# I2Cbus.net
KiCad netlist of a schematic drawn in Altium Designer
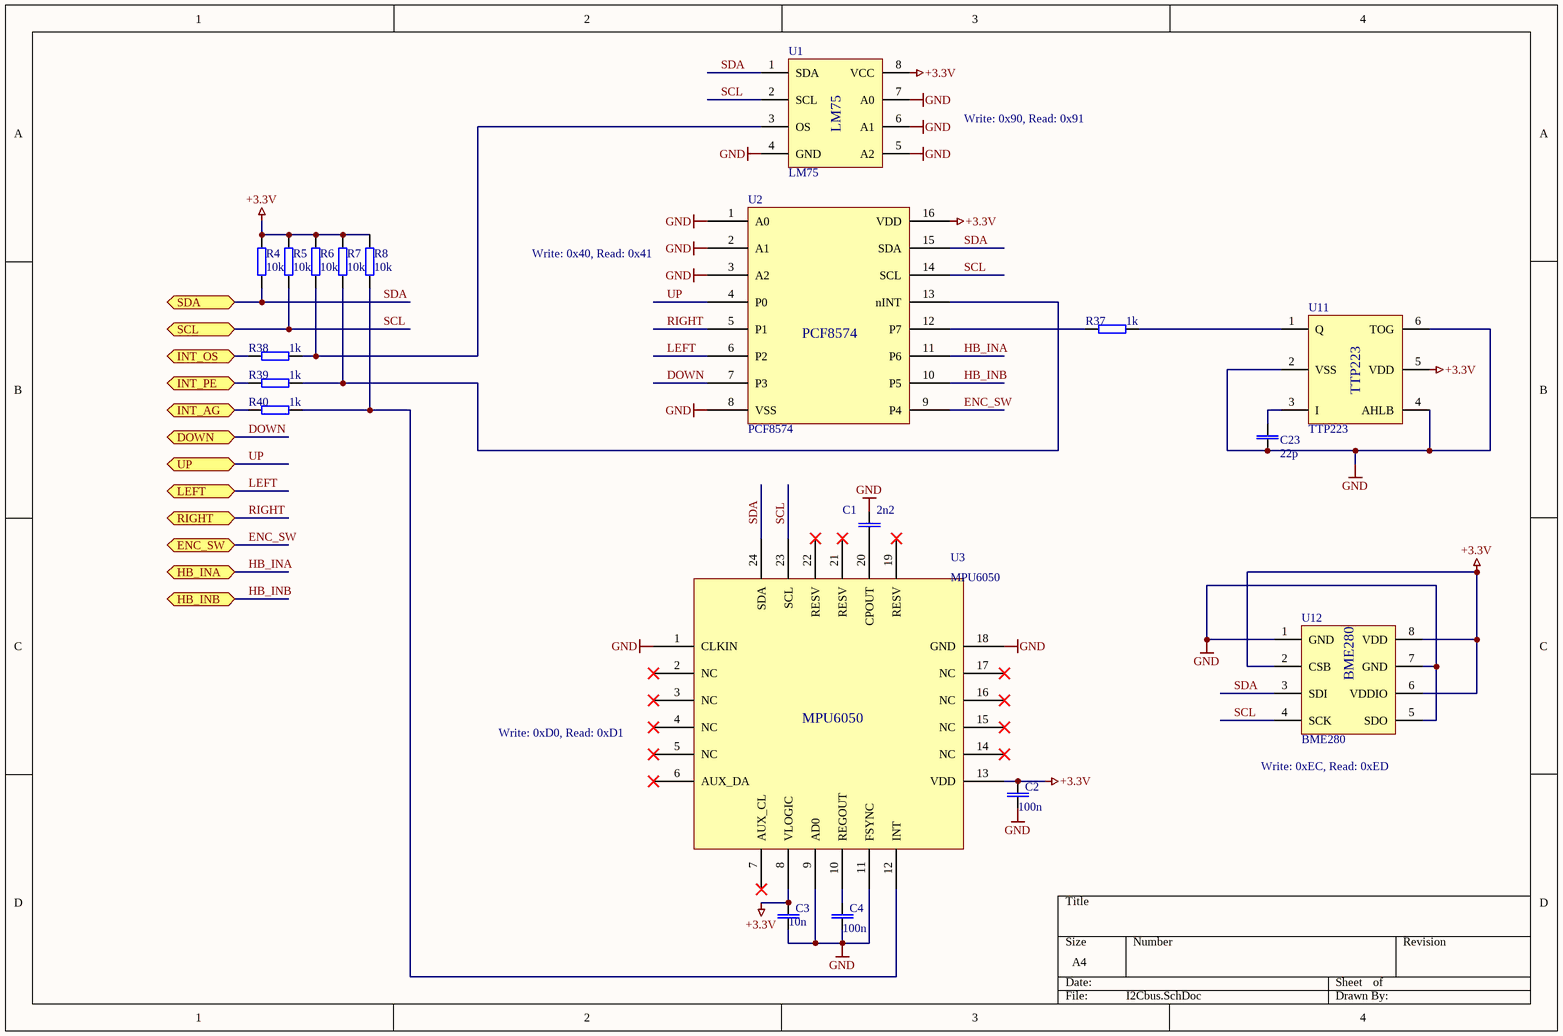
[diagram p0: I2Cbus.SchDoc]

(export (version "E")
  (design (tool "Eeschema 10.0.6"))
  (components
    (comp (ref "C1")
      (value "2n2")
      (footprint "CAP 0805")
      (description "NON POLARIZED CAPACITOR")
      (libsource (lib "SCH_LIB") (part "CAP"))
    )
    (comp (ref "C2")
      (value "100n")
      (footprint "CAP 0805")
      (description "NON POLARIZED CAPACITOR")
      (libsource (lib "SCH_LIB") (part "CAP"))
    )
    (comp (ref "C3")
      (value "10n")
      (footprint "CAP 0805")
      (description "NON POLARIZED CAPACITOR")
      (libsource (lib "SCH_LIB") (part "CAP"))
    )
    (comp (ref "C4")
      (value "100n")
      (footprint "CAP 0805")
      (description "NON POLARIZED CAPACITOR")
      (libsource (lib "SCH_LIB") (part "CAP"))
    )
    (comp (ref "C23")
      (value "22p")
      (footprint "CAP 0805")
      (description "NON POLARIZED CAPACITOR")
      (libsource (lib "SCH_LIB") (part "CAP"))
    )
    (comp (ref "R4")
      (value "10k")
      (footprint "RES 0805")
      (description "RESISTOR")
      (libsource (lib "") (part "RES_1"))
    )
    (comp (ref "R5")
      (value "10k")
      (footprint "RES 0805")
      (description "RESISTOR")
      (libsource (lib "") (part "RES_1"))
    )
    (comp (ref "R6")
      (value "10k")
      (footprint "RES 0805")
      (description "RESISTOR")
      (libsource (lib "") (part "RES_1"))
    )
    (comp (ref "R7")
      (value "10k")
      (footprint "RES 0805")
      (description "RESISTOR")
      (libsource (lib "") (part "RES_1"))
    )
    (comp (ref "R8")
      (value "10k")
      (footprint "RES 0805")
      (description "RESISTOR")
      (libsource (lib "") (part "RES_1"))
    )
    (comp (ref "R37")
      (value "1k")
      (footprint "RES 0805")
      (description "RESISTOR")
      (libsource (lib "SCH_LIB") (part "RES"))
    )
    (comp (ref "R38")
      (value "1k")
      (footprint "RES 0805")
      (description "RESISTOR")
      (libsource (lib "SCH_LIB") (part "RES"))
    )
    (comp (ref "R39")
      (value "1k")
      (footprint "RES 0805")
      (description "RESISTOR")
      (libsource (lib "SCH_LIB") (part "RES"))
    )
    (comp (ref "R40")
      (value "1k")
      (footprint "RES 0805")
      (description "RESISTOR")
      (libsource (lib "SCH_LIB") (part "RES"))
    )
    (comp (ref "U1")
      (value "LM75")
      (footprint "SO8")
      (description "Temperature sensor with I2C interface")
      (libsource (lib "SCH_LIB") (part "LM75"))
    )
    (comp (ref "U2")
      (value "PCF8574")
      (footprint "SO16W")
      (description "I/O expander I2C bus")
      (libsource (lib "SCH_LIB") (part "PCF8574"))
    )
    (comp (ref "U3")
      (value "MPU6050")
      (footprint "QFN24")
      (description "6 axis gyroscope and accelerometer sensor")
      (libsource (lib "SCH_LIB") (part "MPU6050"))
    )
    (comp (ref "U11")
      (value "TTP223")
      (footprint "SOT-23-6L")
      (description "1 KEY TOUCH PAD DETECTOR IC")
      (libsource (lib "SCH_LIB") (part "TTP223"))
    )
    (comp (ref "U12")
      (value "BME280")
      (footprint "BME280")
      (description "BME280 Environmental sensor")
      (libsource (lib "SCH_LIB") (part "BME280"))
    )
  )
  (nets
    (net (code "1") (name "+3.3V") (class "Default")
      (node (ref "C2") (pin "1") (pinfunction "1_1") (pintype "passive"))
      (node (ref "C3") (pin "1") (pinfunction "1_1") (pintype "passive"))
      (node (ref "R4") (pin "2") (pinfunction "2_2") (pintype "passive"))
      (node (ref "R5") (pin "2") (pinfunction "2_2") (pintype "passive"))
      (node (ref "R6") (pin "2") (pinfunction "2_2") (pintype "passive"))
      (node (ref "R7") (pin "2") (pinfunction "2_2") (pintype "passive"))
      (node (ref "R8") (pin "2") (pinfunction "2_2") (pintype "passive"))
      (node (ref "U1") (pin "8") (pinfunction "VCC_8") (pintype "passive"))
      (node (ref "U11") (pin "5") (pinfunction "VDD_5") (pintype "passive"))
      (node (ref "U12") (pin "2") (pinfunction "CSB_2") (pintype "passive"))
      (node (ref "U12") (pin "6") (pinfunction "VDDIO_6") (pintype "passive"))
      (node (ref "U12") (pin "8") (pinfunction "VDD_8") (pintype "passive"))
      (node (ref "U2") (pin "16") (pinfunction "VDD_16") (pintype "passive"))
      (node (ref "U3") (pin "13") (pinfunction "VDD_13") (pintype "passive"))
      (node (ref "U3") (pin "8") (pinfunction "VLOGIC_8") (pintype "passive"))
    )
    (net (code "2") (name "/DOWN") (class "Default")
      (node (ref "U2") (pin "7") (pinfunction "P3_7") (pintype "passive"))
    )
    (net (code "3") (name "/ENC_SW") (class "Default")
      (node (ref "U2") (pin "9") (pinfunction "P4_9") (pintype "passive"))
    )
    (net (code "4") (name "/HB_INA") (class "Default")
      (node (ref "U2") (pin "11") (pinfunction "P6_11") (pintype "passive"))
    )
    (net (code "5") (name "/HB_INB") (class "Default")
      (node (ref "U2") (pin "10") (pinfunction "P5_10") (pintype "passive"))
    )
    (net (code "6") (name "/INT_AG") (class "Default")
      (node (ref "R40") (pin "1") (pinfunction "1_1") (pintype "passive"))
    )
    (net (code "7") (name "/INT_OS") (class "Default")
      (node (ref "R38") (pin "1") (pinfunction "1_1") (pintype "passive"))
    )
    (net (code "8") (name "/INT_PE") (class "Default")
      (node (ref "R39") (pin "1") (pinfunction "1_1") (pintype "passive"))
    )
    (net (code "9") (name "/LEFT") (class "Default")
      (node (ref "U2") (pin "6") (pinfunction "P2_6") (pintype "passive"))
    )
    (net (code "10") (name "/RIGHT") (class "Default")
      (node (ref "U2") (pin "5") (pinfunction "P1_5") (pintype "passive"))
    )
    (net (code "11") (name "/SCL") (class "Default")
      (node (ref "R5") (pin "1") (pinfunction "1_1") (pintype "passive"))
      (node (ref "U1") (pin "2") (pinfunction "SCL_2") (pintype "passive"))
      (node (ref "U12") (pin "4") (pinfunction "SCK_4") (pintype "passive"))
      (node (ref "U2") (pin "14") (pinfunction "SCL_14") (pintype "passive"))
      (node (ref "U3") (pin "23") (pinfunction "SCL_23") (pintype "passive"))
    )
    (net (code "12") (name "/SDA") (class "Default")
      (node (ref "R4") (pin "1") (pinfunction "1_1") (pintype "passive"))
      (node (ref "U1") (pin "1") (pinfunction "SDA_1") (pintype "passive"))
      (node (ref "U12") (pin "3") (pinfunction "SDI_3") (pintype "passive"))
      (node (ref "U2") (pin "15") (pinfunction "SDA_15") (pintype "passive"))
      (node (ref "U3") (pin "24") (pinfunction "SDA_24") (pintype "passive"))
    )
    (net (code "13") (name "/UP") (class "Default")
      (node (ref "U2") (pin "4") (pinfunction "P0_4") (pintype "passive"))
    )
    (net (code "14") (name "GND") (class "Default")
      (node (ref "C1") (pin "2") (pinfunction "2_2") (pintype "passive"))
      (node (ref "C2") (pin "2") (pinfunction "2_2") (pintype "passive"))
      (node (ref "C23") (pin "2") (pinfunction "2_2") (pintype "passive"))
      (node (ref "C3") (pin "2") (pinfunction "2_2") (pintype "passive"))
      (node (ref "C4") (pin "2") (pinfunction "2_2") (pintype "passive"))
      (node (ref "U1") (pin "4") (pinfunction "GND_4") (pintype "passive"))
      (node (ref "U1") (pin "5") (pinfunction "A2_5") (pintype "passive"))
      (node (ref "U1") (pin "6") (pinfunction "A1_6") (pintype "passive"))
      (node (ref "U1") (pin "7") (pinfunction "A0_7") (pintype "passive"))
      (node (ref "U11") (pin "2") (pinfunction "VSS_2") (pintype "passive"))
      (node (ref "U11") (pin "4") (pinfunction "AHLB_4") (pintype "passive"))
      (node (ref "U11") (pin "6") (pinfunction "TOG_6") (pintype "passive"))
      (node (ref "U12") (pin "1") (pinfunction "GND_1") (pintype "passive"))
      (node (ref "U12") (pin "5") (pinfunction "SDO_5") (pintype "passive"))
      (node (ref "U12") (pin "7") (pinfunction "GND_7") (pintype "passive"))
      (node (ref "U2") (pin "1") (pinfunction "A0_1") (pintype "passive"))
      (node (ref "U2") (pin "2") (pinfunction "A1_2") (pintype "passive"))
      (node (ref "U2") (pin "3") (pinfunction "A2_3") (pintype "passive"))
      (node (ref "U2") (pin "8") (pinfunction "VSS_8") (pintype "passive"))
      (node (ref "U3") (pin "1") (pinfunction "CLKIN_1") (pintype "passive"))
      (node (ref "U3") (pin "11") (pinfunction "FSYNC_11") (pintype "passive"))
      (node (ref "U3") (pin "18") (pinfunction "GND_18") (pintype "passive"))
      (node (ref "U3") (pin "9") (pinfunction "AD0_9") (pintype "passive"))
    )
    (net (code "15") (name "Net-(U1-OS)") (class "Default")
      (node (ref "R38") (pin "2") (pinfunction "2_2") (pintype "passive"))
      (node (ref "R6") (pin "1") (pinfunction "1_1") (pintype "passive"))
      (node (ref "U1") (pin "3") (pinfunction "OS_3") (pintype "passive"))
    )
    (net (code "16") (name "Net-(U2-P7)") (class "Default")
      (node (ref "R37") (pin "1") (pinfunction "1_1") (pintype "passive"))
      (node (ref "U2") (pin "12") (pinfunction "P7_12") (pintype "passive"))
    )
    (net (code "17") (name "Net-(U2-nINT)") (class "Default")
      (node (ref "R39") (pin "2") (pinfunction "2_2") (pintype "passive"))
      (node (ref "R7") (pin "1") (pinfunction "1_1") (pintype "passive"))
      (node (ref "U2") (pin "13") (pinfunction "nINT_13") (pintype "passive"))
    )
    (net (code "18") (name "Net-(U3-CPOUT)") (class "Default")
      (node (ref "C1") (pin "1") (pinfunction "1_1") (pintype "passive"))
      (node (ref "U3") (pin "20") (pinfunction "CPOUT_20") (pintype "passive"))
    )
    (net (code "19") (name "Net-(U3-INT)") (class "Default")
      (node (ref "R40") (pin "2") (pinfunction "2_2") (pintype "passive"))
      (node (ref "R8") (pin "1") (pinfunction "1_1") (pintype "passive"))
      (node (ref "U3") (pin "12") (pinfunction "INT_12") (pintype "passive"))
    )
    (net (code "20") (name "Net-(U3-REGOUT)") (class "Default")
      (node (ref "C4") (pin "1") (pinfunction "1_1") (pintype "passive"))
      (node (ref "U3") (pin "10") (pinfunction "REGOUT_10") (pintype "passive"))
    )
    (net (code "21") (name "Net-(U11-I)") (class "Default")
      (node (ref "C23") (pin "1") (pinfunction "1_1") (pintype "passive"))
      (node (ref "U11") (pin "3") (pinfunction "I_3") (pintype "passive"))
    )
    (net (code "22") (name "Net-(U11-Q)") (class "Default")
      (node (ref "R37") (pin "2") (pinfunction "2_2") (pintype "passive"))
      (node (ref "U11") (pin "1") (pinfunction "Q_1") (pintype "passive"))
    )
    (net (code "23") (name "unconnected-(U3-AUX_CL-Pad7)") (class "Default")
      (node (ref "U3") (pin "7") (pinfunction "AUX_CL_7") (pintype "passive+no_connect"))
    )
    (net (code "24") (name "unconnected-(U3-AUX_DA-Pad6)") (class "Default")
      (node (ref "U3") (pin "6") (pinfunction "AUX_DA_6") (pintype "passive+no_connect"))
    )
    (net (code "25") (name "unconnected-(U3-NC-Pad2)") (class "Default")
      (node (ref "U3") (pin "2") (pinfunction "NC_2") (pintype "passive+no_connect"))
    )
    (net (code "26") (name "unconnected-(U3-NC-Pad3)") (class "Default")
      (node (ref "U3") (pin "3") (pinfunction "NC_3") (pintype "passive+no_connect"))
    )
    (net (code "27") (name "unconnected-(U3-NC-Pad4)") (class "Default")
      (node (ref "U3") (pin "4") (pinfunction "NC_4") (pintype "passive+no_connect"))
    )
    (net (code "28") (name "unconnected-(U3-NC-Pad5)") (class "Default")
      (node (ref "U3") (pin "5") (pinfunction "NC_5") (pintype "passive+no_connect"))
    )
    (net (code "29") (name "unconnected-(U3-NC-Pad14)") (class "Default")
      (node (ref "U3") (pin "14") (pinfunction "NC_14") (pintype "passive+no_connect"))
    )
    (net (code "30") (name "unconnected-(U3-NC-Pad15)") (class "Default")
      (node (ref "U3") (pin "15") (pinfunction "NC_15") (pintype "passive+no_connect"))
    )
    (net (code "31") (name "unconnected-(U3-NC-Pad16)") (class "Default")
      (node (ref "U3") (pin "16") (pinfunction "NC_16") (pintype "passive+no_connect"))
    )
    (net (code "32") (name "unconnected-(U3-NC-Pad17)") (class "Default")
      (node (ref "U3") (pin "17") (pinfunction "NC_17") (pintype "passive+no_connect"))
    )
    (net (code "33") (name "unconnected-(U3-RESV-Pad19)") (class "Default")
      (node (ref "U3") (pin "19") (pinfunction "RESV_19") (pintype "passive+no_connect"))
    )
    (net (code "34") (name "unconnected-(U3-RESV-Pad21)") (class "Default")
      (node (ref "U3") (pin "21") (pinfunction "RESV_21") (pintype "passive+no_connect"))
    )
    (net (code "35") (name "unconnected-(U3-RESV-Pad22)") (class "Default")
      (node (ref "U3") (pin "22") (pinfunction "RESV_22") (pintype "passive+no_connect"))
    )
  )
)
